# Dreamcast.net
KiCad netlist of a schematic drawn in EAGLE
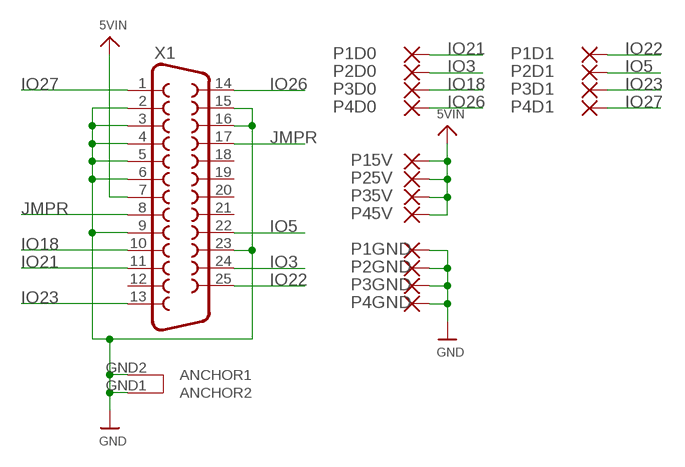
[diagram p0: schematic, sheet 1]

(export (version "E")
  (design (tool "Eeschema 10.0.6"))
  (components
    (comp (ref "P1D0")
      (value "SMD5")
      (footprint "eagle-import:SMD2,54-5,08")
      (libsource (lib "eagle-import") (part "SMD5"))
    )
    (comp (ref "P1D1")
      (value "SMD5")
      (footprint "eagle-import:SMD2,54-5,08")
      (libsource (lib "eagle-import") (part "SMD5"))
    )
    (comp (ref "P1GND")
      (value "SMD5")
      (footprint "eagle-import:SMD2,54-5,08")
      (libsource (lib "eagle-import") (part "SMD5"))
    )
    (comp (ref "P2D0")
      (value "SMD5")
      (footprint "eagle-import:SMD2,54-5,08")
      (libsource (lib "eagle-import") (part "SMD5"))
    )
    (comp (ref "P2D1")
      (value "SMD5")
      (footprint "eagle-import:SMD2,54-5,08")
      (libsource (lib "eagle-import") (part "SMD5"))
    )
    (comp (ref "P2GND")
      (value "SMD5")
      (footprint "eagle-import:SMD2,54-5,08")
      (libsource (lib "eagle-import") (part "SMD5"))
    )
    (comp (ref "P3D0")
      (value "SMD5")
      (footprint "eagle-import:SMD2,54-5,08")
      (libsource (lib "eagle-import") (part "SMD5"))
    )
    (comp (ref "P3D1")
      (value "SMD5")
      (footprint "eagle-import:SMD2,54-5,08")
      (libsource (lib "eagle-import") (part "SMD5"))
    )
    (comp (ref "P3GND")
      (value "SMD5")
      (footprint "eagle-import:SMD2,54-5,08")
      (libsource (lib "eagle-import") (part "SMD5"))
    )
    (comp (ref "P4D0")
      (value "SMD5")
      (footprint "eagle-import:SMD2,54-5,08")
      (libsource (lib "eagle-import") (part "SMD5"))
    )
    (comp (ref "P4D1")
      (value "SMD5")
      (footprint "eagle-import:SMD2,54-5,08")
      (libsource (lib "eagle-import") (part "SMD5"))
    )
    (comp (ref "P4GND")
      (value "SMD5")
      (footprint "eagle-import:SMD2,54-5,08")
      (libsource (lib "eagle-import") (part "SMD5"))
    )
    (comp (ref "P15V")
      (value "SMD5")
      (footprint "eagle-import:SMD2,54-5,08")
      (libsource (lib "eagle-import") (part "SMD5"))
    )
    (comp (ref "P25V")
      (value "SMD5")
      (footprint "eagle-import:SMD2,54-5,08")
      (libsource (lib "eagle-import") (part "SMD5"))
    )
    (comp (ref "P35V")
      (value "SMD5")
      (footprint "eagle-import:SMD2,54-5,08")
      (libsource (lib "eagle-import") (part "SMD5"))
    )
    (comp (ref "P45V")
      (value "SMD5")
      (footprint "eagle-import:SMD2,54-5,08")
      (libsource (lib "eagle-import") (part "SMD5"))
    )
    (comp (ref "X1")
      (value "DB25_FEMALEHP")
      (footprint "eagle-import:F25HP")
      (libsource (lib "eagle-import") (part "DB25_FEMALEHP"))
    )
  )
  (nets
    (net (code "1") (name "/IO3") (class "Default")
      (node (ref "P2D0") (pin "1") (pinfunction "P_1") (pintype "passive"))
      (node (ref "X1") (pin "24") (pinfunction "24_24") (pintype "passive"))
    )
    (net (code "2") (name "/IO5") (class "Default")
      (node (ref "P2D1") (pin "1") (pinfunction "P_1") (pintype "passive"))
      (node (ref "X1") (pin "22") (pinfunction "22_22") (pintype "passive"))
    )
    (net (code "3") (name "/IO18") (class "Default")
      (node (ref "P3D0") (pin "1") (pinfunction "P_1") (pintype "passive"))
      (node (ref "X1") (pin "10") (pinfunction "10_10") (pintype "passive"))
    )
    (net (code "4") (name "/IO21") (class "Default")
      (node (ref "P1D0") (pin "1") (pinfunction "P_1") (pintype "passive"))
      (node (ref "X1") (pin "11") (pinfunction "11_11") (pintype "passive"))
    )
    (net (code "5") (name "/IO22") (class "Default")
      (node (ref "P1D1") (pin "1") (pinfunction "P_1") (pintype "passive"))
      (node (ref "X1") (pin "25") (pinfunction "25_25") (pintype "passive"))
    )
    (net (code "6") (name "/IO23") (class "Default")
      (node (ref "P3D1") (pin "1") (pinfunction "P_1") (pintype "passive"))
      (node (ref "X1") (pin "13") (pinfunction "13_13") (pintype "passive"))
    )
    (net (code "7") (name "/IO26") (class "Default")
      (node (ref "P4D0") (pin "1") (pinfunction "P_1") (pintype "passive"))
      (node (ref "X1") (pin "14") (pinfunction "14_14") (pintype "passive"))
    )
    (net (code "8") (name "/IO27") (class "Default")
      (node (ref "P4D1") (pin "1") (pinfunction "P_1") (pintype "passive"))
      (node (ref "X1") (pin "1") (pinfunction "1_1") (pintype "passive"))
    )
    (net (code "9") (name "/JMPR") (class "Default")
      (node (ref "X1") (pin "17") (pinfunction "17_17") (pintype "passive"))
      (node (ref "X1") (pin "8") (pinfunction "8_8") (pintype "passive"))
    )
    (net (code "10") (name "5VIN") (class "Default")
      (node (ref "P15V") (pin "1") (pinfunction "P_1") (pintype "passive"))
      (node (ref "P25V") (pin "1") (pinfunction "P_1") (pintype "passive"))
      (node (ref "P35V") (pin "1") (pinfunction "P_1") (pintype "passive"))
      (node (ref "P45V") (pin "1") (pinfunction "P_1") (pintype "passive"))
      (node (ref "X1") (pin "7") (pinfunction "7_7") (pintype "passive"))
    )
    (net (code "11") (name "GND") (class "Default")
      (node (ref "P1GND") (pin "1") (pinfunction "P_1") (pintype "passive"))
      (node (ref "P2GND") (pin "1") (pinfunction "P_1") (pintype "passive"))
      (node (ref "P3GND") (pin "1") (pinfunction "P_1") (pintype "passive"))
      (node (ref "P4GND") (pin "1") (pinfunction "P_1") (pintype "passive"))
      (node (ref "X1") (pin "15") (pinfunction "15_15") (pintype "passive"))
      (node (ref "X1") (pin "16") (pinfunction "16_16") (pintype "passive"))
      (node (ref "X1") (pin "2") (pinfunction "2_2") (pintype "passive"))
      (node (ref "X1") (pin "23") (pinfunction "23_23") (pintype "passive"))
      (node (ref "X1") (pin "3") (pinfunction "3_3") (pintype "passive"))
      (node (ref "X1") (pin "4") (pinfunction "4_4") (pintype "passive"))
      (node (ref "X1") (pin "5") (pinfunction "5_5") (pintype "passive"))
      (node (ref "X1") (pin "6") (pinfunction "6_6") (pintype "passive"))
      (node (ref "X1") (pin "9") (pinfunction "9_9") (pintype "passive"))
      (node (ref "X1") (pin "GND1") (pinfunction "ANCHOR2_GND1") (pintype "bidirectional"))
      (node (ref "X1") (pin "GND2") (pinfunction "ANCHOR1_GND2") (pintype "bidirectional"))
    )
    (net (code "12") (name "unconnected-(X1-Pad12)") (class "Default")
      (node (ref "X1") (pin "12") (pinfunction "12_12") (pintype "passive"))
    )
    (net (code "13") (name "unconnected-(X1-Pad18)") (class "Default")
      (node (ref "X1") (pin "18") (pinfunction "18_18") (pintype "passive"))
    )
    (net (code "14") (name "unconnected-(X1-Pad19)") (class "Default")
      (node (ref "X1") (pin "19") (pinfunction "19_19") (pintype "passive"))
    )
    (net (code "15") (name "unconnected-(X1-Pad20)") (class "Default")
      (node (ref "X1") (pin "20") (pinfunction "20_20") (pintype "passive"))
    )
    (net (code "16") (name "unconnected-(X1-Pad21)") (class "Default")
      (node (ref "X1") (pin "21") (pinfunction "21_21") (pintype "passive"))
    )
  )
)
